# Sensors.net
KiCad netlist of a schematic drawn in Altium Designer
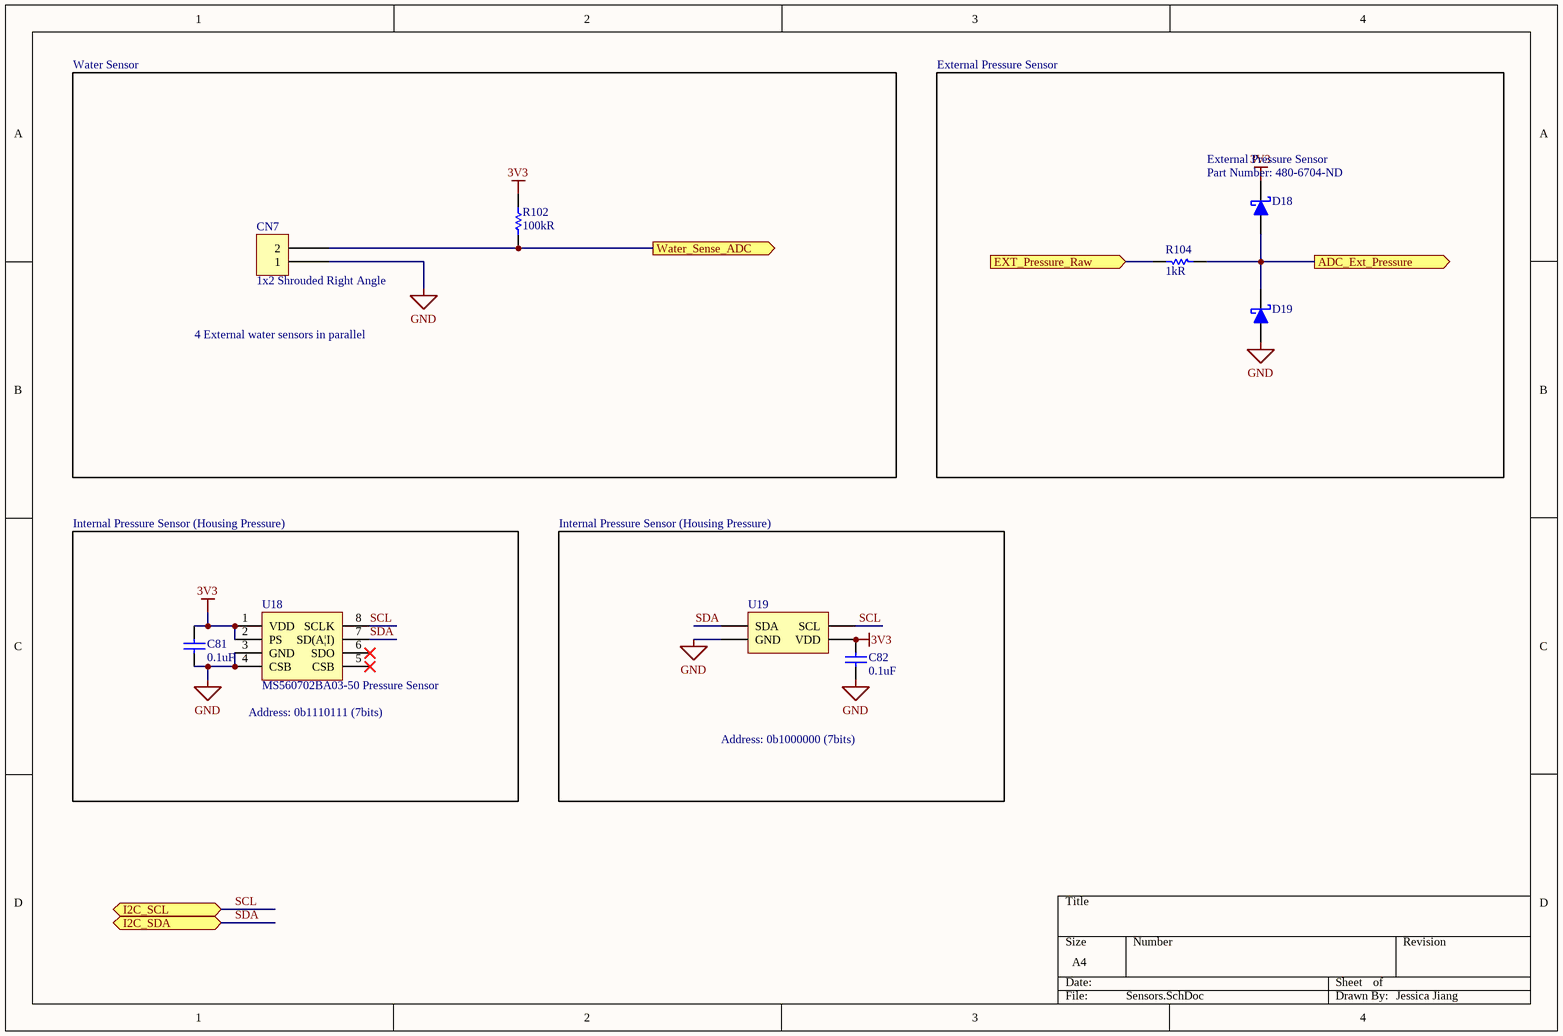
[diagram p0: Sensors.SchDoc]

(export (version "E")
  (design (tool "Eeschema 10.0.6"))
  (components
    (comp (ref "C81")
      (value "CL10B104JB8NNNC")
      (footprint "FP-CL10-0_1-IPC_A")
      (description "CAP CER 0.1UF 50V X7R 0603")
      (fields
        (field (name "TOLERANCE") "5%")
        (field (name "VOLTAGE") "50V")
        (field (name "CAPACITANCE") "0.1uF")
      )
      (libsource (lib "AUVIC") (part "CAP-NP-2"))
    )
    (comp (ref "C82")
      (value "CL10B104JB8NNNC")
      (footprint "FP-CL10-0_1-IPC_A")
      (description "CAP CER 0.1UF 50V X7R 0603")
      (fields
        (field (name "TOLERANCE") "5%")
        (field (name "VOLTAGE") "50V")
        (field (name "CAPACITANCE") "0.1uF")
      )
      (libsource (lib "AUVIC") (part "CAP-NP-2"))
    )
    (comp (ref "CN7")
      (value "1x2 Shrouded Right Angle")
      (footprint "2X1 Female Header")
      (description "02 MTE HDR SRRA LATCH")
      (libsource (lib "AUVIC") (part "1x2 Shrouded Right Angle"))
    )
    (comp (ref "D18")
      (value "CUS08F30,H3F")
      (footprint "SC-76")
      (description "Diode Schottky 30V 800mA Surface Mount USC")
      (libsource (lib "AUVIC") (part "Symbol"))
    )
    (comp (ref "D19")
      (value "CUS08F30,H3F")
      (footprint "SC-76")
      (description "Diode Schottky 30V 800mA Surface Mount USC")
      (libsource (lib "AUVIC") (part "Symbol"))
    )
    (comp (ref "R102")
      (value "CRCW0603-100KFKEA")
      (footprint "RESC1609X50X30ML10T20")
      (description "Resistor; Thick Film; 100 Kilohms; 0.1 W; 1%; SMT; 0603; TCR 37 ppm/DegC; Tape and Reel")
      (fields (field (name "RESISTANCE") "100kR") (field (name "TOLERANCE") "1%"))
      (libsource (lib "AUVIC") (part "RES"))
    )
    (comp (ref "R104")
      (value "ERJ3EKF1001V")
      (footprint "RESC1608X55X30ML15T15")
      (description "Res Thick Film 0603 1K Ohm 1% 1/10W ±100ppm/°C Molded SMD Punched Carrier T/R")
      (fields (field (name "RESISTANCE") "1kR") (field (name "TOLERANCE") "1%"))
      (libsource (lib "AUVIC") (part "RES"))
    )
    (comp (ref "U18")
      (value "MS560702BA03-50 Pressure Sensor")
      (footprint "TE Pressure Sensor (MS560702BA03-50)")
      (description "1kPa to 120 kPa")
      (fields (field (name "MADE BY") "Andy Bates"))
      (libsource (lib "") (part "Symbol_1"))
    )
    (comp (ref "U19")
      (value "Si700XX")
      (footprint "QFN-6")
      (description "I2C Humidity and Temperature Sensor")
      (fields (field (name "MADE BY") "Andy Bates"))
      (libsource (lib "AUVIC") (part "Si700XX"))
    )
  )
  (nets
    (net (code "1") (name "/ADC_Ext_Pressure") (class "Default")
      (node (ref "D18") (pin "A") (pinfunction "Anode_A") (pintype "passive"))
      (node (ref "D19") (pin "K") (pinfunction "Cathode_K") (pintype "passive"))
      (node (ref "R104") (pin "1") (pinfunction "1_1") (pintype "passive"))
    )
    (net (code "2") (name "/EXT_Pressure_Raw") (class "Default")
      (node (ref "R104") (pin "2") (pinfunction "2_2") (pintype "passive"))
    )
    (net (code "3") (name "/SCL") (class "Default")
      (node (ref "U18") (pin "8") (pinfunction "SCLK_8") (pintype "passive"))
      (node (ref "U19") (pin "6") (pinfunction "SCL_6") (pintype "passive"))
    )
    (net (code "4") (name "/SDA") (class "Default")
      (node (ref "U18") (pin "7") (pinfunction "SD(A¦I)_7") (pintype "passive"))
      (node (ref "U19") (pin "1") (pinfunction "SDA_1") (pintype "passive"))
    )
    (net (code "5") (name "/Water_Sense_ADC") (class "Default")
      (node (ref "CN7") (pin "2") (pinfunction "2_2") (pintype "passive"))
      (node (ref "R102") (pin "1") (pinfunction "1_1") (pintype "passive"))
    )
    (net (code "6") (name "3V3") (class "Default")
      (node (ref "C81") (pin "1") (pinfunction "1_1") (pintype "passive"))
      (node (ref "C82") (pin "1") (pinfunction "1_1") (pintype "passive"))
      (node (ref "D18") (pin "K") (pinfunction "Cathode_K") (pintype "passive"))
      (node (ref "R102") (pin "2") (pinfunction "2_2") (pintype "passive"))
      (node (ref "U18") (pin "1") (pinfunction "VDD_1") (pintype "passive"))
      (node (ref "U18") (pin "2") (pinfunction "PS_2") (pintype "passive"))
      (node (ref "U19") (pin "5") (pinfunction "VDD_5") (pintype "passive"))
    )
    (net (code "7") (name "GND") (class "Default")
      (node (ref "C81") (pin "2") (pinfunction "2_2") (pintype "passive"))
      (node (ref "C82") (pin "2") (pinfunction "2_2") (pintype "passive"))
      (node (ref "CN7") (pin "1") (pinfunction "1_1") (pintype "passive"))
      (node (ref "D19") (pin "A") (pinfunction "Anode_A") (pintype "passive"))
      (node (ref "U18") (pin "3") (pinfunction "GND_3") (pintype "passive"))
      (node (ref "U18") (pin "4") (pinfunction "CSB_4") (pintype "passive"))
      (node (ref "U19") (pin "2") (pinfunction "GND_2") (pintype "passive"))
    )
    (net (code "8") (name "unconnected-(U18-CSB-Pad5)") (class "Default")
      (node (ref "U18") (pin "5") (pinfunction "CSB_5") (pintype "passive+no_connect"))
    )
    (net (code "9") (name "unconnected-(U18-SDO-Pad6)") (class "Default")
      (node (ref "U18") (pin "6") (pinfunction "SDO_6") (pintype "passive+no_connect"))
    )
  )
)
